# Driver_Morpheu_v4_0_PONTE_H.net
KiCad netlist of a schematic drawn in Altium Designer
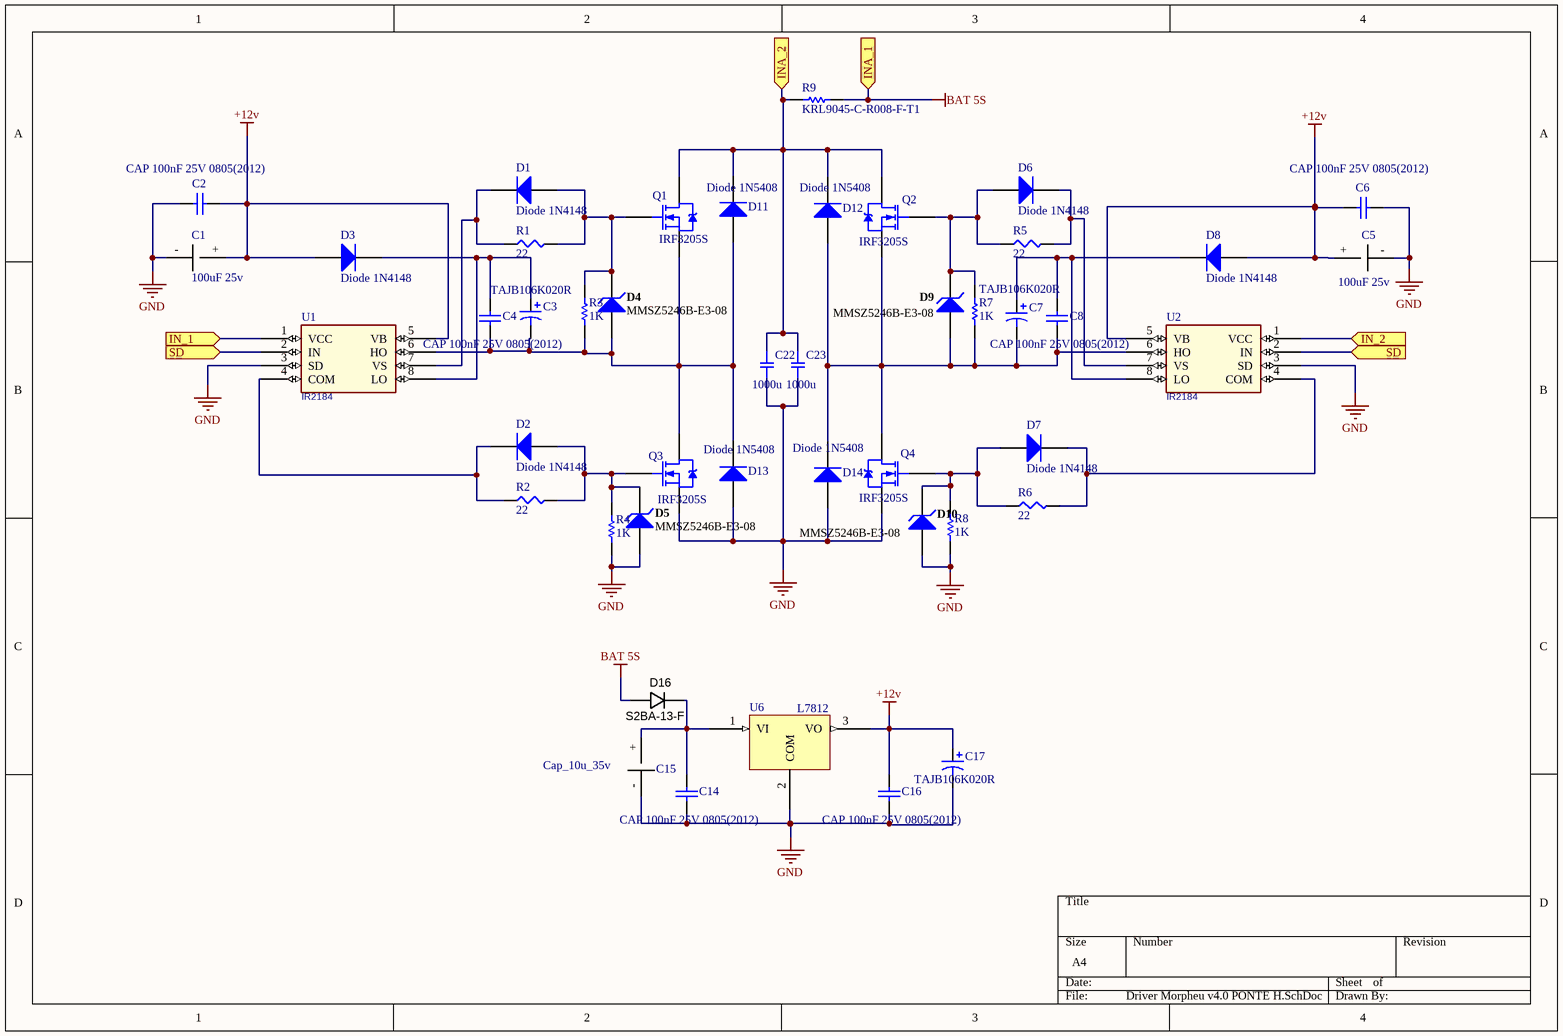
[diagram p0: Driver Morpheu v4.0 PONTE H.SchDoc]

(export (version "E")
  (design (tool "Eeschema 10.0.6"))
  (components
    (comp (ref "C1")
      (value "100uF 25v")
      (footprint "CAP_100u_25v_Tantalum")
      (description "Cap Tântalo")
      (libsource (lib "LibSanhaço2017") (part "Cap_100u_25v"))
    )
    (comp (ref "C2")
      (value "CAP 100nF 25V 0805(2012)")
      (footprint "CAPC0805(2012)145_M")
      (description "CAP 100nF 25V ±5% 0805 (2012 Metric) Thickness 1.45mm SMD")
      (fields (field (name "TOLERANCE") "Â±5%"))
      (libsource (lib "Altium Content Vault") (part "CAP"))
    )
    (comp (ref "C3")
      (value "TAJB106K020R")
      (footprint "AVX-CAPC3528_V")
      (description "Capacitor, Tantalum, 10uF 10% 20V MCCT-B (3528)")
      (fields (field (name "MANUFACTURER") "AVX") (field (name "TOLERANCE") "10%"))
      (libsource (lib "Altium Content Vault") (part "AVX-CAP-P-2"))
    )
    (comp (ref "C4")
      (value "CAP 100nF 25V 0805(2012)")
      (footprint "CAPC0805(2012)145_M")
      (description "CAP 100nF 25V ±5% 0805 (2012 Metric) Thickness 1.45mm SMD")
      (fields (field (name "TOLERANCE") "Â±5%"))
      (libsource (lib "Altium Content Vault") (part "CAP"))
    )
    (comp (ref "C5")
      (value "100uF 25v")
      (footprint "CAP_100u_25v_Tantalum")
      (description "Cap Tântalo")
      (libsource (lib "LibSanhaço2017") (part "Cap_100u_25v"))
    )
    (comp (ref "C6")
      (value "CAP 100nF 25V 0805(2012)")
      (footprint "CAPC0805(2012)145_M")
      (description "CAP 100nF 25V ±5% 0805 (2012 Metric) Thickness 1.45mm SMD")
      (fields (field (name "TOLERANCE") "Â±5%"))
      (libsource (lib "Altium Content Vault") (part "CAP"))
    )
    (comp (ref "C7")
      (value "TAJB106K020R")
      (footprint "AVX-CAPC3528_V")
      (description "Capacitor, Tantalum, 10uF 10% 20V MCCT-B (3528)")
      (fields (field (name "MANUFACTURER") "AVX") (field (name "TOLERANCE") "10%"))
      (libsource (lib "Altium Content Vault") (part "AVX-CAP-P-2"))
    )
    (comp (ref "C8")
      (value "CAP 100nF 25V 0805(2012)")
      (footprint "CAPC0805(2012)145_M")
      (description "CAP 100nF 25V ±5% 0805 (2012 Metric) Thickness 1.45mm SMD")
      (fields (field (name "TOLERANCE") "Â±5%"))
      (libsource (lib "Altium Content Vault") (part "CAP"))
    )
    (comp (ref "C14")
      (value "CAP 100nF 25V 0805(2012)")
      (footprint "CAPC0805(2012)145_M")
      (description "CAP 100nF 25V ±5% 0805 (2012 Metric) Thickness 1.45mm SMD")
      (fields (field (name "TOLERANCE") "Â±5%"))
      (libsource (lib "Altium Content Vault") (part "CAP"))
    )
    (comp (ref "C15")
      (value "Cap_10u_35v")
      (footprint "CAP_100u_25v_Tantalum")
      (libsource (lib "LibSanhaço2017") (part "Cap_10u_35v"))
    )
    (comp (ref "C16")
      (value "CAP 100nF 25V 0805(2012)")
      (footprint "CAPC0805(2012)145_M")
      (description "CAP 100nF 25V ±5% 0805 (2012 Metric) Thickness 1.45mm SMD")
      (fields (field (name "TOLERANCE") "Â±5%"))
      (libsource (lib "Altium Content Vault") (part "CAP"))
    )
    (comp (ref "C17")
      (value "TAJB106K020R")
      (footprint "AVX-CAPC3528_V")
      (description "Capacitor, Tantalum, 10uF 10% 20V MCCT-B (3528)")
      (fields (field (name "MANUFACTURER") "AVX") (field (name "TOLERANCE") "10%"))
      (libsource (lib "Altium Content Vault") (part "AVX-CAP-P-2"))
    )
    (comp (ref "C22")
      (value "1000u")
      (footprint "CAPAE250P680X1220_FLAT1")
      (description "CAP MLCC SMT")
      (libsource (lib "capacitor_dblib") (part "CAPACITOR"))
    )
    (comp (ref "C23")
      (value "1000u")
      (footprint "CAPAE250P680X1220_FLAT1")
      (description "CAP MLCC SMT")
      (libsource (lib "capacitor_dblib") (part "CAPACITOR"))
    )
    (comp (ref "D1")
      (value "Diode 1N4148")
      (footprint "SOD123")
      (description "High Conductance Fast Diode")
      (fields (field (name "PUBLISHER") "Altium Limited"))
      (libsource (lib "Miscellaneous Devices") (part "Diode 1N4148"))
    )
    (comp (ref "D2")
      (value "Diode 1N4148")
      (footprint "SOD123")
      (description "High Conductance Fast Diode")
      (fields (field (name "PUBLISHER") "Altium Limited"))
      (libsource (lib "Miscellaneous Devices") (part "Diode 1N4148"))
    )
    (comp (ref "D3")
      (value "Diode 1N4148")
      (footprint "SOD123")
      (description "High Conductance Fast Diode")
      (fields (field (name "PUBLISHER") "Altium Limited"))
      (libsource (lib "Miscellaneous Devices") (part "Diode 1N4148"))
    )
    (comp (ref "D4")
      (value "MMSZ5246B-E3-08")
      (footprint "VISH-SOD-123-2_V")
      (description "Small Signal Zener Diode, 16 V +/- 5%, -55 to 155 degC, 2-Pin SOD-123, RoHS, Tape and Reel")
      (fields (field (name "MANUFACTURER") "Vishay Semiconductor") (field (name "TOLERANCE") "+/- 5%"))
      (libsource (lib "Altium Content Vault") (part "VISH-DZEN_A1K2-2"))
    )
    (comp (ref "D5")
      (value "MMSZ5246B-E3-08")
      (footprint "VISH-SOD-123-2_V")
      (description "Small Signal Zener Diode, 16 V +/- 5%, -55 to 155 degC, 2-Pin SOD-123, RoHS, Tape and Reel")
      (fields (field (name "MANUFACTURER") "Vishay Semiconductor") (field (name "TOLERANCE") "+/- 5%"))
      (libsource (lib "Altium Content Vault") (part "VISH-DZEN_A1K2-2"))
    )
    (comp (ref "D6")
      (value "Diode 1N4148")
      (footprint "SOD123")
      (description "High Conductance Fast Diode")
      (fields (field (name "PUBLISHER") "Altium Limited"))
      (libsource (lib "Miscellaneous Devices") (part "Diode 1N4148"))
    )
    (comp (ref "D7")
      (value "Diode 1N4148")
      (footprint "SOD123")
      (description "High Conductance Fast Diode")
      (fields (field (name "PUBLISHER") "Altium Limited"))
      (libsource (lib "Miscellaneous Devices") (part "Diode 1N4148"))
    )
    (comp (ref "D8")
      (value "Diode 1N4148")
      (footprint "SOD123")
      (description "High Conductance Fast Diode")
      (fields (field (name "PUBLISHER") "Altium Limited"))
      (libsource (lib "Miscellaneous Devices") (part "Diode 1N4148"))
    )
    (comp (ref "D9")
      (value "MMSZ5246B-E3-08")
      (footprint "VISH-SOD-123-2_V")
      (description "Small Signal Zener Diode, 16 V +/- 5%, -55 to 155 degC, 2-Pin SOD-123, RoHS, Tape and Reel")
      (fields (field (name "MANUFACTURER") "Vishay Semiconductor") (field (name "TOLERANCE") "+/- 5%"))
      (libsource (lib "Altium Content Vault") (part "CMP-0931-00032-1"))
    )
    (comp (ref "D10")
      (value "MMSZ5246B-E3-08")
      (footprint "VISH-SOD-123-2_V")
      (description "Small Signal Zener Diode, 16 V +/- 5%, -55 to 155 degC, 2-Pin SOD-123, RoHS, Tape and Reel")
      (fields (field (name "MANUFACTURER") "Vishay Semiconductor") (field (name "TOLERANCE") "+/- 5%"))
      (libsource (lib "Altium Content Vault") (part "VISH-DZEN_A1K2-2"))
    )
    (comp (ref "D11")
      (value "Diode 1N5408")
      (footprint "DO-201AD")
      (description "3 Amp Medium Power Silicon Rectifier Diode")
      (fields (field (name "PUBLISHER") "Altium Limited"))
      (libsource (lib "Miscellaneous Devices") (part "Diode 1N5408"))
    )
    (comp (ref "D12")
      (value "Diode 1N5408")
      (footprint "DO-201AD")
      (description "3 Amp Medium Power Silicon Rectifier Diode")
      (fields (field (name "PUBLISHER") "Altium Limited"))
      (libsource (lib "Miscellaneous Devices") (part "Diode 1N5408"))
    )
    (comp (ref "D13")
      (value "Diode 1N5408")
      (footprint "DO-201AD")
      (description "3 Amp Medium Power Silicon Rectifier Diode")
      (fields (field (name "PUBLISHER") "Altium Limited"))
      (libsource (lib "Miscellaneous Devices") (part "Diode 1N5408"))
    )
    (comp (ref "D14")
      (value "Diode 1N5408")
      (footprint "DO-201AD")
      (description "3 Amp Medium Power Silicon Rectifier Diode")
      (fields (field (name "PUBLISHER") "Altium Limited"))
      (libsource (lib "Miscellaneous Devices") (part "Diode 1N5408"))
    )
    (comp (ref "D16")
      (value "100V; 1.5A")
      (footprint "DO-214AC")
      (description "Diode SMD 100V 1.5A SMA")
      (fields (field (name "MANUFACTURER PART NUMBER 1") "S2BA-13-F"))
      (libsource (lib "PBL - Diodes") (part "DIODE_100V_1.5A_SMA"))
    )
    (comp (ref "Q1")
      (value "IRF3205S")
      (footprint "D2PAK_N")
      (description "HEXFET Power MOSFET")
      (fields (field (name "PUBLISHER") "Altium Limited"))
      (libsource (lib "IR Discrete MOSFET - Power") (part "IRF3205S"))
    )
    (comp (ref "Q2")
      (value "IRF3205S")
      (footprint "D2PAK_N")
      (description "HEXFET Power MOSFET")
      (fields (field (name "PUBLISHER") "Altium Limited"))
      (libsource (lib "IR Discrete MOSFET - Power") (part "IRF3205S"))
    )
    (comp (ref "Q3")
      (value "IRF3205S")
      (footprint "D2PAK_N")
      (description "HEXFET Power MOSFET")
      (fields (field (name "PUBLISHER") "Altium Limited"))
      (libsource (lib "IR Discrete MOSFET - Power") (part "IRF3205S"))
    )
    (comp (ref "Q4")
      (value "IRF3205S")
      (footprint "D2PAK_N")
      (description "HEXFET Power MOSFET")
      (fields (field (name "PUBLISHER") "Altium Limited"))
      (libsource (lib "IR Discrete MOSFET - Power") (part "IRF3205S"))
    )
    (comp (ref "R1")
      (value "22")
      (footprint "SMD-0603-RES")
      (description "RES SMD 22 OHM 1% 1/10W 0603")
      (fields
        (field (name "PART NUMBER") "ERJ-3EKF22R0V")
        (field (name "DIGI-KEY PART NUMBER") "P22.0HCT-ND")
      )
      (libsource (lib "Panasonic_ERJ_0603") (part "ERJ-3EKF22R0V"))
    )
    (comp (ref "R2")
      (value "22")
      (footprint "SMD-0603-RES")
      (description "RES SMD 22 OHM 1% 1/10W 0603")
      (fields
        (field (name "PART NUMBER") "ERJ-3EKF22R0V")
        (field (name "DIGI-KEY PART NUMBER") "P22.0HCT-ND")
      )
      (libsource (lib "Panasonic_ERJ_0603") (part "ERJ-3EKF22R0V"))
    )
    (comp (ref "R3")
      (value "1K")
      (footprint "RES-0402")
      (description "RES SMD 1K OHM 5% 1/16W 0402")
      (fields (field (name "Comment") "RC0402JR-071KL"))
      (libsource (lib "Schlib1") (part "RES 1K 0402"))
    )
    (comp (ref "R4")
      (value "1K")
      (footprint "RES-0402")
      (description "RES SMD 1K OHM 5% 1/16W 0402")
      (fields (field (name "Comment") "RC0402JR-071KL"))
      (libsource (lib "Schlib1") (part "RES 1K 0402"))
    )
    (comp (ref "R5")
      (value "22")
      (footprint "SMD-0603-RES")
      (description "RES SMD 22 OHM 1% 1/10W 0603")
      (fields
        (field (name "PART NUMBER") "ERJ-3EKF22R0V")
        (field (name "DIGI-KEY PART NUMBER") "P22.0HCT-ND")
      )
      (libsource (lib "Panasonic_ERJ_0603") (part "ERJ-3EKF22R0V"))
    )
    (comp (ref "R6")
      (value "22")
      (footprint "SMD-0603-RES")
      (description "RES SMD 22 OHM 1% 1/10W 0603")
      (fields
        (field (name "PART NUMBER") "ERJ-3EKF22R0V")
        (field (name "DIGI-KEY PART NUMBER") "P22.0HCT-ND")
      )
      (libsource (lib "Panasonic_ERJ_0603") (part "ERJ-3EKF22R0V"))
    )
    (comp (ref "R7")
      (value "1K")
      (footprint "RES-0402")
      (description "RES SMD 1K OHM 5% 1/16W 0402")
      (fields (field (name "Comment") "RC0402JR-071KL"))
      (libsource (lib "Schlib1") (part "RES 1K 0402"))
    )
    (comp (ref "R8")
      (value "1K")
      (footprint "RES-0402")
      (description "RES SMD 1K OHM 5% 1/16W 0402")
      (fields (field (name "Comment") "RC0402JR-071KL"))
      (libsource (lib "Schlib1") (part "RES 1K 0402"))
    )
    (comp (ref "R9")
      (value "KRL9045-C-R008-F-T1")
      (footprint "8m OHM 4W")
      (description "Chip Resistor, 0.008 Ohm, +/- 1%, 4 W")
      (fields (field (name "TOLERANCE") "1%") (field (name "PARTNUMBER") "WSLP12061L000FEA"))
      (libsource (lib "altium-import") (part "root_2_RES-2_"))
    )
    (comp (ref "U1")
      (value "IR2184")
      (footprint "SOIC127P600X175-8AN")
      (libsource (lib "") (part "IR2184_1"))
    )
    (comp (ref "U2")
      (value "IR2184")
      (footprint "SOIC127P600X175-8AN")
      (libsource (lib "IR2184") (part "IR2184"))
    )
    (comp (ref "U6") (value "L7812") (footprint "D2PAK-3") (libsource (lib "78XX") (part "LM7812")))
  )
  (nets
    (net (code "1") (name "+12v") (class "Default")
      (node (ref "C1") (pin "+") (pintype "passive"))
      (node (ref "C16") (pin "2") (pinfunction "2_2") (pintype "passive"))
      (node (ref "C17") (pin "1") (pinfunction "1_1") (pintype "passive"))
      (node (ref "C2") (pin "2") (pinfunction "2_2") (pintype "passive"))
      (node (ref "C5") (pin "+") (pintype "passive"))
      (node (ref "C6") (pin "2") (pinfunction "2_2") (pintype "passive"))
      (node (ref "D3") (pin "1") (pinfunction "A_1") (pintype "passive"))
      (node (ref "D8") (pin "1") (pinfunction "A_1") (pintype "passive"))
      (node (ref "U1") (pin "5") (pinfunction "VB_5") (pintype "bidirectional"))
      (node (ref "U2") (pin "5") (pinfunction "VB_5") (pintype "bidirectional"))
      (node (ref "U6") (pin "3") (pinfunction "VO_3") (pintype "output"))
    )
    (net (code "2") (name "/INA_2") (class "Default")
      (node (ref "C22") (pin "1") (pinfunction "1_1") (pintype "passive"))
      (node (ref "C23") (pin "1") (pinfunction "1_1") (pintype "passive"))
      (node (ref "D11") (pin "2") (pinfunction "K_2") (pintype "passive"))
      (node (ref "D12") (pin "2") (pinfunction "K_2") (pintype "passive"))
      (node (ref "Q1") (pin "2") (pinfunction "D_2") (pintype "passive"))
      (node (ref "Q2") (pin "2") (pinfunction "D_2") (pintype "passive"))
      (node (ref "R9") (pin "2") (pinfunction "2_2") (pintype "passive"))
    )
    (net (code "3") (name "/IN_1") (class "Default")
      (node (ref "U1") (pin "1") (pinfunction "VCC_1") (pintype "bidirectional"))
    )
    (net (code "4") (name "/IN_2") (class "Default")
      (node (ref "U2") (pin "1") (pinfunction "VCC_1") (pintype "bidirectional"))
    )
    (net (code "5") (name "/SD") (class "Default")
      (node (ref "U1") (pin "2") (pinfunction "IN_2") (pintype "bidirectional"))
      (node (ref "U2") (pin "2") (pinfunction "IN_2") (pintype "bidirectional"))
    )
    (net (code "6") (name "BAT 5S") (class "Default")
      (node (ref "D16") (pin "A") (pinfunction "A_A") (pintype "passive"))
      (node (ref "R9") (pin "1") (pinfunction "1_1") (pintype "passive"))
    )
    (net (code "7") (name "GND") (class "Default")
      (node (ref "C1") (pin "-") (pintype "passive"))
      (node (ref "C14") (pin "1") (pinfunction "1_1") (pintype "passive"))
      (node (ref "C15") (pin "-") (pintype "passive"))
      (node (ref "C16") (pin "1") (pinfunction "1_1") (pintype "passive"))
      (node (ref "C17") (pin "2") (pinfunction "2_2") (pintype "passive"))
      (node (ref "C2") (pin "1") (pinfunction "1_1") (pintype "passive"))
      (node (ref "C22") (pin "2") (pinfunction "2_2") (pintype "passive"))
      (node (ref "C23") (pin "2") (pinfunction "2_2") (pintype "passive"))
      (node (ref "C5") (pin "-") (pintype "passive"))
      (node (ref "C6") (pin "1") (pinfunction "1_1") (pintype "passive"))
      (node (ref "D10") (pin "1") (pinfunction "A_1") (pintype "passive"))
      (node (ref "D13") (pin "1") (pinfunction "A_1") (pintype "passive"))
      (node (ref "D14") (pin "1") (pinfunction "A_1") (pintype "passive"))
      (node (ref "D5") (pin "1") (pinfunction "A_1") (pintype "passive"))
      (node (ref "Q3") (pin "3") (pinfunction "S_3") (pintype "passive"))
      (node (ref "Q4") (pin "3") (pinfunction "S_3") (pintype "passive"))
      (node (ref "R4") (pin "1") (pinfunction "1_1") (pintype "passive"))
      (node (ref "R8") (pin "1") (pinfunction "1_1") (pintype "passive"))
      (node (ref "U1") (pin "3") (pinfunction "SD_3") (pintype "bidirectional"))
      (node (ref "U2") (pin "3") (pinfunction "SD_3") (pintype "bidirectional"))
      (node (ref "U6") (pin "2") (pinfunction "COM_2") (pintype "power_in"))
    )
    (net (code "8") (name "Net-(D1-A)") (class "Default")
      (node (ref "D1") (pin "1") (pinfunction "A_1") (pintype "passive"))
      (node (ref "D4") (pin "2") (pinfunction "K_2") (pintype "passive"))
      (node (ref "Q1") (pin "1") (pinfunction "G_1") (pintype "passive"))
      (node (ref "R1") (pin "2") (pinfunction "2_2") (pintype "passive"))
      (node (ref "R3") (pin "2") (pinfunction "2_2") (pintype "passive"))
    )
    (net (code "9") (name "Net-(D1-K)") (class "Default")
      (node (ref "D1") (pin "2") (pinfunction "K_2") (pintype "passive"))
      (node (ref "R1") (pin "1") (pinfunction "1_1") (pintype "passive"))
      (node (ref "U1") (pin "7") (pinfunction "VS_7") (pintype "bidirectional"))
    )
    (net (code "10") (name "Net-(D2-A)") (class "Default")
      (node (ref "D2") (pin "1") (pinfunction "A_1") (pintype "passive"))
      (node (ref "D5") (pin "2") (pinfunction "K_2") (pintype "passive"))
      (node (ref "Q3") (pin "1") (pinfunction "G_1") (pintype "passive"))
      (node (ref "R2") (pin "2") (pinfunction "2_2") (pintype "passive"))
      (node (ref "R4") (pin "2") (pinfunction "2_2") (pintype "passive"))
    )
    (net (code "11") (name "Net-(D2-K)") (class "Default")
      (node (ref "D2") (pin "2") (pinfunction "K_2") (pintype "passive"))
      (node (ref "R2") (pin "1") (pinfunction "1_1") (pintype "passive"))
      (node (ref "U1") (pin "4") (pinfunction "COM_4") (pintype "bidirectional"))
    )
    (net (code "12") (name "Net-(D3-K)") (class "Default")
      (node (ref "C3") (pin "1") (pinfunction "1_1") (pintype "passive"))
      (node (ref "C4") (pin "2") (pinfunction "2_2") (pintype "passive"))
      (node (ref "D3") (pin "2") (pinfunction "K_2") (pintype "passive"))
      (node (ref "U1") (pin "8") (pinfunction "LO_8") (pintype "bidirectional"))
    )
    (net (code "13") (name "Net-(D6-A)") (class "Default")
      (node (ref "D6") (pin "1") (pinfunction "A_1") (pintype "passive"))
      (node (ref "D9") (pin "2") (pinfunction "K_2") (pintype "passive"))
      (node (ref "Q2") (pin "1") (pinfunction "G_1") (pintype "passive"))
      (node (ref "R5") (pin "1") (pinfunction "1_1") (pintype "passive"))
      (node (ref "R7") (pin "2") (pinfunction "2_2") (pintype "passive"))
    )
    (net (code "14") (name "Net-(D6-K)") (class "Default")
      (node (ref "D6") (pin "2") (pinfunction "K_2") (pintype "passive"))
      (node (ref "R5") (pin "2") (pinfunction "2_2") (pintype "passive"))
      (node (ref "U2") (pin "7") (pinfunction "VS_7") (pintype "bidirectional"))
    )
    (net (code "15") (name "Net-(D7-K)") (class "Default")
      (node (ref "D7") (pin "2") (pinfunction "K_2") (pintype "passive"))
      (node (ref "R6") (pin "2") (pinfunction "2_2") (pintype "passive"))
      (node (ref "U2") (pin "4") (pinfunction "COM_4") (pintype "bidirectional"))
    )
    (net (code "16") (name "Net-(D8-K)") (class "Default")
      (node (ref "C7") (pin "1") (pinfunction "1_1") (pintype "passive"))
      (node (ref "C8") (pin "2") (pinfunction "2_2") (pintype "passive"))
      (node (ref "D8") (pin "2") (pinfunction "K_2") (pintype "passive"))
      (node (ref "U2") (pin "8") (pinfunction "LO_8") (pintype "bidirectional"))
    )
    (net (code "17") (name "Net-(D10-K)") (class "Default")
      (node (ref "D10") (pin "2") (pinfunction "K_2") (pintype "passive"))
      (node (ref "D7") (pin "1") (pinfunction "A_1") (pintype "passive"))
      (node (ref "Q4") (pin "1") (pinfunction "G_1") (pintype "passive"))
      (node (ref "R6") (pin "1") (pinfunction "1_1") (pintype "passive"))
      (node (ref "R8") (pin "2") (pinfunction "2_2") (pintype "passive"))
    )
    (net (code "18") (name "Net-(D11-A)") (class "Default")
      (node (ref "C3") (pin "2") (pinfunction "2_2") (pintype "passive"))
      (node (ref "C4") (pin "1") (pinfunction "1_1") (pintype "passive"))
      (node (ref "D11") (pin "1") (pinfunction "A_1") (pintype "passive"))
      (node (ref "D13") (pin "2") (pinfunction "K_2") (pintype "passive"))
      (node (ref "D4") (pin "1") (pinfunction "A_1") (pintype "passive"))
      (node (ref "Q1") (pin "3") (pinfunction "S_3") (pintype "passive"))
      (node (ref "Q3") (pin "2") (pinfunction "D_2") (pintype "passive"))
      (node (ref "R3") (pin "1") (pinfunction "1_1") (pintype "passive"))
      (node (ref "U1") (pin "6") (pinfunction "HO_6") (pintype "bidirectional"))
    )
    (net (code "19") (name "Net-(D12-A)") (class "Default")
      (node (ref "C7") (pin "2") (pinfunction "2_2") (pintype "passive"))
      (node (ref "C8") (pin "1") (pinfunction "1_1") (pintype "passive"))
      (node (ref "D12") (pin "1") (pinfunction "A_1") (pintype "passive"))
      (node (ref "D14") (pin "2") (pinfunction "K_2") (pintype "passive"))
      (node (ref "D9") (pin "1") (pinfunction "A_1") (pintype "passive"))
      (node (ref "Q2") (pin "3") (pinfunction "S_3") (pintype "passive"))
      (node (ref "Q4") (pin "2") (pinfunction "D_2") (pintype "passive"))
      (node (ref "R7") (pin "1") (pinfunction "1_1") (pintype "passive"))
      (node (ref "U2") (pin "6") (pinfunction "HO_6") (pintype "bidirectional"))
    )
    (net (code "20") (name "Net-(U6-VI)") (class "Default")
      (node (ref "C14") (pin "2") (pinfunction "2_2") (pintype "passive"))
      (node (ref "C15") (pin "+") (pintype "passive"))
      (node (ref "D16") (pin "K") (pinfunction "K_K") (pintype "passive"))
      (node (ref "U6") (pin "1") (pinfunction "VI_1") (pintype "input"))
    )
  )
)
